# arduheater.net
KiCad netlist of a schematic drawn in EAGLE
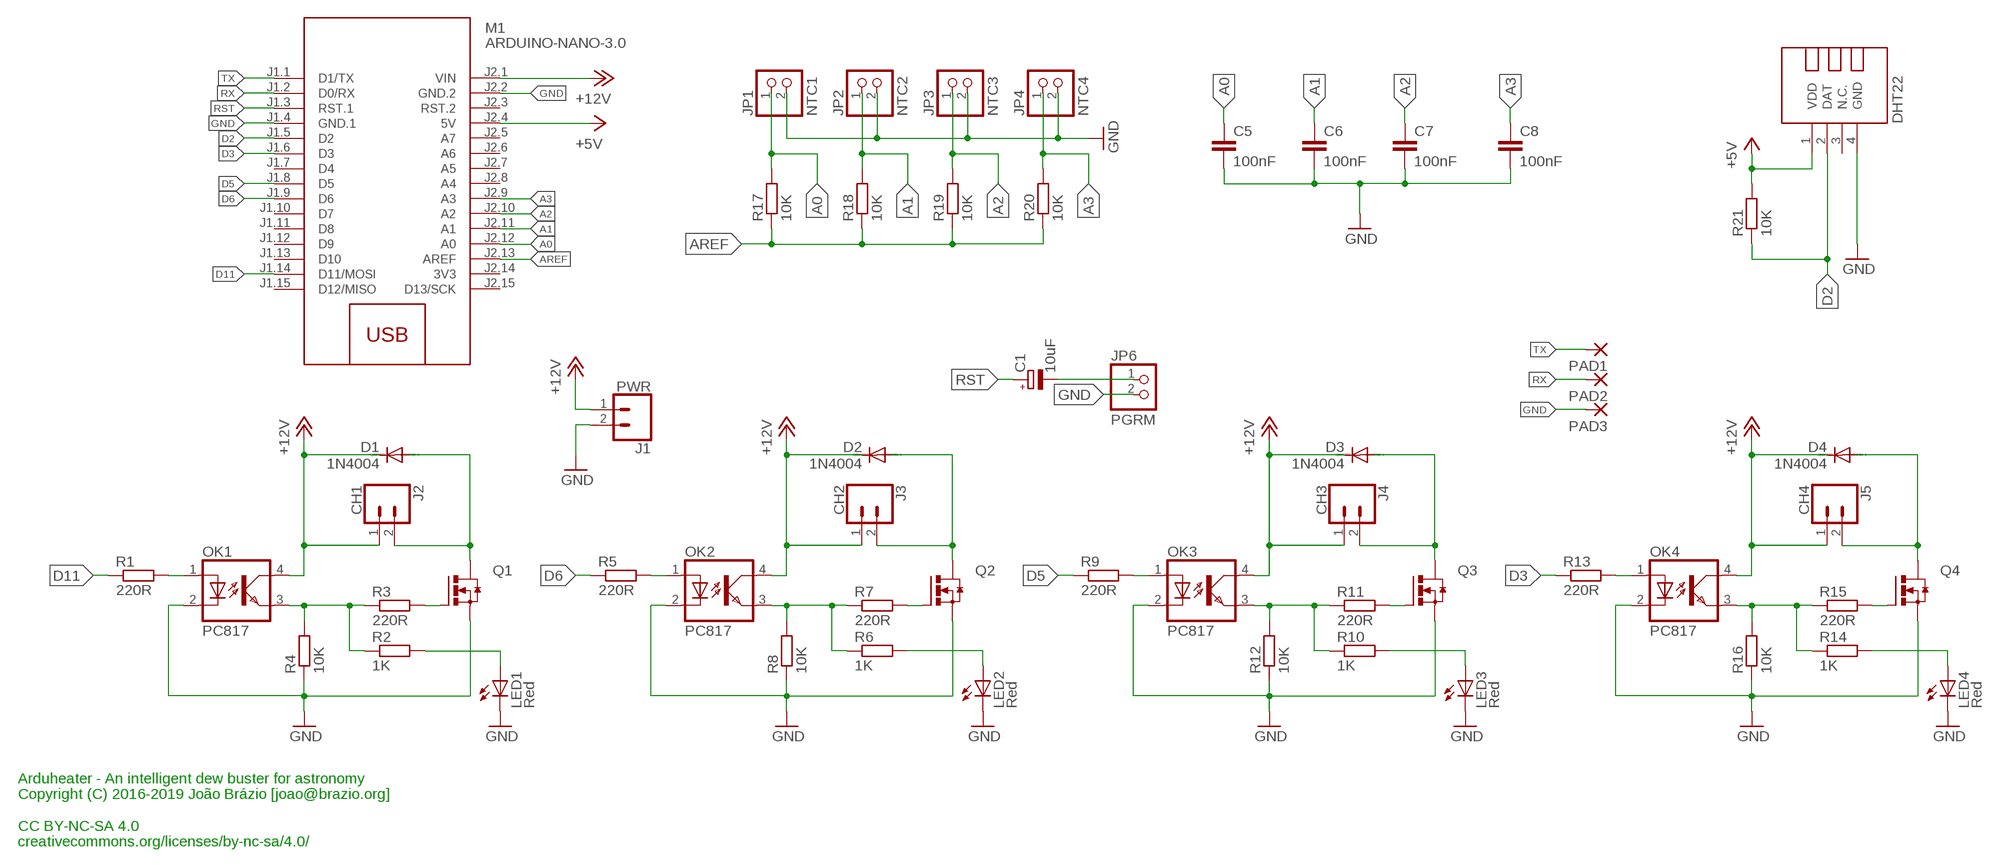
[diagram p0: schematic, sheet 1]

(export (version "E")
  (design (tool "Eeschema 10.0.6"))
  (components
    (comp (ref "C1")
      (value "10uF")
      (footprint "eagle-import:E2,5-6E")
      (libsource (lib "eagle-import") (part "CPOL-EUE2,5-6E"))
    )
    (comp (ref "C5")
      (value "100nF")
      (footprint "eagle-import:C3216")
      (libsource (lib "eagle-import") (part "C-EUC3216"))
    )
    (comp (ref "C6")
      (value "100nF")
      (footprint "eagle-import:C3216")
      (libsource (lib "eagle-import") (part "C-EUC3216"))
    )
    (comp (ref "C7")
      (value "100nF")
      (footprint "eagle-import:C3216")
      (libsource (lib "eagle-import") (part "C-EUC3216"))
    )
    (comp (ref "C8")
      (value "100nF")
      (footprint "eagle-import:C3216")
      (libsource (lib "eagle-import") (part "C-EUC3216"))
    )
    (comp (ref "D1")
      (value "1N4004")
      (footprint "eagle-import:DO41-10")
      (libsource (lib "eagle-import") (part "1N4004"))
    )
    (comp (ref "D2")
      (value "1N4004")
      (footprint "eagle-import:DO41-10")
      (libsource (lib "eagle-import") (part "1N4004"))
    )
    (comp (ref "D3")
      (value "1N4004")
      (footprint "eagle-import:DO41-10")
      (libsource (lib "eagle-import") (part "1N4004"))
    )
    (comp (ref "D4")
      (value "1N4004")
      (footprint "eagle-import:DO41-10")
      (libsource (lib "eagle-import") (part "1N4004"))
    )
    (comp (ref "DHT22")
      (value "TEMP-HUM-SENSOR-DHT22")
      (footprint "eagle-import:TEMP-HUM-SENSOR-DHT22")
      (libsource (lib "eagle-import") (part "TEMP-HUM-SENSOR-DHT22"))
    )
    (comp (ref "J1")
      (value "PWR")
      (footprint "eagle-import:SCREWTERMINAL-5MM-2")
      (libsource (lib "eagle-import") (part "CONN_025MM"))
    )
    (comp (ref "J2")
      (value "CH1")
      (footprint "eagle-import:SCREWTERMINAL-5MM-2")
      (libsource (lib "eagle-import") (part "CONN_025MM"))
    )
    (comp (ref "J3")
      (value "CH2")
      (footprint "eagle-import:SCREWTERMINAL-5MM-2")
      (libsource (lib "eagle-import") (part "CONN_025MM"))
    )
    (comp (ref "J4")
      (value "CH3")
      (footprint "eagle-import:SCREWTERMINAL-5MM-2")
      (libsource (lib "eagle-import") (part "CONN_025MM"))
    )
    (comp (ref "J5")
      (value "CH4")
      (footprint "eagle-import:SCREWTERMINAL-5MM-2")
      (libsource (lib "eagle-import") (part "CONN_025MM"))
    )
    (comp (ref "JP1")
      (value "NTC1")
      (footprint "eagle-import:1X02")
      (libsource (lib "eagle-import") (part "PINHD-1X2"))
    )
    (comp (ref "JP2")
      (value "NTC2")
      (footprint "eagle-import:1X02")
      (libsource (lib "eagle-import") (part "PINHD-1X2"))
    )
    (comp (ref "JP3")
      (value "NTC3")
      (footprint "eagle-import:1X02")
      (libsource (lib "eagle-import") (part "PINHD-1X2"))
    )
    (comp (ref "JP4")
      (value "NTC4")
      (footprint "eagle-import:1X02")
      (libsource (lib "eagle-import") (part "PINHD-1X2"))
    )
    (comp (ref "JP6")
      (value "PGRM")
      (footprint "eagle-import:1X02")
      (libsource (lib "eagle-import") (part "PINHD-1X2"))
    )
    (comp (ref "LED1")
      (value "Red")
      (footprint "eagle-import:LED5MM")
      (libsource (lib "eagle-import") (part "LED5MM"))
    )
    (comp (ref "LED2")
      (value "Red")
      (footprint "eagle-import:LED5MM")
      (libsource (lib "eagle-import") (part "LED5MM"))
    )
    (comp (ref "LED3")
      (value "Red")
      (footprint "eagle-import:LED5MM")
      (libsource (lib "eagle-import") (part "LED5MM"))
    )
    (comp (ref "LED4")
      (value "Red")
      (footprint "eagle-import:LED5MM")
      (libsource (lib "eagle-import") (part "LED5MM"))
    )
    (comp (ref "M1")
      (value "ARDUINO-NANO-3.0")
      (footprint "eagle-import:ARDUINO-NANO-3.0")
      (libsource (lib "eagle-import") (part "ARDUINO-NANO-3.0"))
    )
    (comp (ref "OK1")
      (value "PC817")
      (footprint "eagle-import:DIL04")
      (fields (field (name "MPN") "PC817X4J000F"))
      (libsource (lib "eagle-import") (part "PC817"))
    )
    (comp (ref "OK2")
      (value "PC817")
      (footprint "eagle-import:DIL04")
      (fields (field (name "MPN") "PC817X4J000F"))
      (libsource (lib "eagle-import") (part "PC817"))
    )
    (comp (ref "OK3")
      (value "PC817")
      (footprint "eagle-import:DIL04")
      (fields (field (name "MPN") "PC817X4J000F"))
      (libsource (lib "eagle-import") (part "PC817"))
    )
    (comp (ref "OK4")
      (value "PC817")
      (footprint "eagle-import:DIL04")
      (fields (field (name "MPN") "PC817X4J000F"))
      (libsource (lib "eagle-import") (part "PC817"))
    )
    (comp (ref "PAD1")
      (value "SMD2")
      (footprint "eagle-import:SMD1,27-2,54")
      (libsource (lib "eagle-import") (part "SMD2"))
    )
    (comp (ref "PAD2")
      (value "SMD2")
      (footprint "eagle-import:SMD1,27-2,54")
      (libsource (lib "eagle-import") (part "SMD2"))
    )
    (comp (ref "PAD3")
      (value "SMD2")
      (footprint "eagle-import:SMD1,27-2,54")
      (libsource (lib "eagle-import") (part "SMD2"))
    )
    (comp (ref "Q1")
      (value "IRF3704L-V")
      (footprint "eagle-import:TO262-V")
      (libsource (lib "eagle-import") (part "IRF3704L-V"))
    )
    (comp (ref "Q2")
      (value "IRF3704L-V")
      (footprint "eagle-import:TO262-V")
      (libsource (lib "eagle-import") (part "IRF3704L-V"))
    )
    (comp (ref "Q3")
      (value "IRF3704L-V")
      (footprint "eagle-import:TO262-V")
      (libsource (lib "eagle-import") (part "IRF3704L-V"))
    )
    (comp (ref "Q4")
      (value "IRF3704L-V")
      (footprint "eagle-import:TO262-V")
      (libsource (lib "eagle-import") (part "IRF3704L-V"))
    )
    (comp (ref "R1")
      (value "220R")
      (footprint "eagle-import:M1206")
      (libsource (lib "eagle-import") (part "R-EU_M1206"))
    )
    (comp (ref "R2")
      (value "1K")
      (footprint "eagle-import:M1206")
      (libsource (lib "eagle-import") (part "R-EU_M1206"))
    )
    (comp (ref "R3")
      (value "220R")
      (footprint "eagle-import:M1206")
      (libsource (lib "eagle-import") (part "R-EU_M1206"))
    )
    (comp (ref "R4")
      (value "10K")
      (footprint "eagle-import:M1206")
      (libsource (lib "eagle-import") (part "R-EU_M1206"))
    )
    (comp (ref "R5")
      (value "220R")
      (footprint "eagle-import:M1206")
      (libsource (lib "eagle-import") (part "R-EU_M1206"))
    )
    (comp (ref "R6")
      (value "1K")
      (footprint "eagle-import:M1206")
      (libsource (lib "eagle-import") (part "R-EU_M1206"))
    )
    (comp (ref "R7")
      (value "220R")
      (footprint "eagle-import:M1206")
      (libsource (lib "eagle-import") (part "R-EU_M1206"))
    )
    (comp (ref "R8")
      (value "10K")
      (footprint "eagle-import:M1206")
      (libsource (lib "eagle-import") (part "R-EU_M1206"))
    )
    (comp (ref "R9")
      (value "220R")
      (footprint "eagle-import:M1206")
      (libsource (lib "eagle-import") (part "R-EU_M1206"))
    )
    (comp (ref "R10")
      (value "1K")
      (footprint "eagle-import:M1206")
      (libsource (lib "eagle-import") (part "R-EU_M1206"))
    )
    (comp (ref "R11")
      (value "220R")
      (footprint "eagle-import:M1206")
      (libsource (lib "eagle-import") (part "R-EU_M1206"))
    )
    (comp (ref "R12")
      (value "10K")
      (footprint "eagle-import:M1206")
      (libsource (lib "eagle-import") (part "R-EU_M1206"))
    )
    (comp (ref "R13")
      (value "220R")
      (footprint "eagle-import:M1206")
      (libsource (lib "eagle-import") (part "R-EU_M1206"))
    )
    (comp (ref "R14")
      (value "1K")
      (footprint "eagle-import:M1206")
      (libsource (lib "eagle-import") (part "R-EU_M1206"))
    )
    (comp (ref "R15")
      (value "220R")
      (footprint "eagle-import:M1206")
      (libsource (lib "eagle-import") (part "R-EU_M1206"))
    )
    (comp (ref "R16")
      (value "10K")
      (footprint "eagle-import:M1206")
      (libsource (lib "eagle-import") (part "R-EU_M1206"))
    )
    (comp (ref "R17")
      (value "10K")
      (footprint "eagle-import:M1206")
      (libsource (lib "eagle-import") (part "R-EU_M1206"))
    )
    (comp (ref "R18")
      (value "10K")
      (footprint "eagle-import:M1206")
      (libsource (lib "eagle-import") (part "R-EU_M1206"))
    )
    (comp (ref "R19")
      (value "10K")
      (footprint "eagle-import:M1206")
      (libsource (lib "eagle-import") (part "R-EU_M1206"))
    )
    (comp (ref "R20")
      (value "10K")
      (footprint "eagle-import:M1206")
      (libsource (lib "eagle-import") (part "R-EU_M1206"))
    )
    (comp (ref "R21")
      (value "10K")
      (footprint "eagle-import:M1206")
      (libsource (lib "eagle-import") (part "R-EU_M1206"))
    )
  )
  (nets
    (net (code "1") (name "+5V") (class "Default")
      (node (ref "DHT22") (pin "1") (pinfunction "VDD_1") (pintype "power_in"))
      (node (ref "M1") (pin "J2.4") (pinfunction "5V_J2.4") (pintype "power_in"))
      (node (ref "R21") (pin "2") (pinfunction "2_2") (pintype "passive"))
    )
    (net (code "2") (name "+12V") (class "Default")
      (node (ref "D1") (pin "C") (pinfunction "C_C") (pintype "passive"))
      (node (ref "D2") (pin "C") (pinfunction "C_C") (pintype "passive"))
      (node (ref "D3") (pin "C") (pinfunction "C_C") (pintype "passive"))
      (node (ref "D4") (pin "C") (pinfunction "C_C") (pintype "passive"))
      (node (ref "J1") (pin "1") (pinfunction "1_1") (pintype "passive"))
      (node (ref "J2") (pin "1") (pinfunction "1_1") (pintype "passive"))
      (node (ref "J3") (pin "1") (pinfunction "1_1") (pintype "passive"))
      (node (ref "J4") (pin "1") (pinfunction "1_1") (pintype "passive"))
      (node (ref "J5") (pin "1") (pinfunction "1_1") (pintype "passive"))
      (node (ref "M1") (pin "J2.1") (pinfunction "VIN_J2.1") (pintype "power_in"))
      (node (ref "OK1") (pin "4") (pinfunction "COL_4") (pintype "passive"))
      (node (ref "OK2") (pin "4") (pinfunction "COL_4") (pintype "passive"))
      (node (ref "OK3") (pin "4") (pinfunction "COL_4") (pintype "passive"))
      (node (ref "OK4") (pin "4") (pinfunction "COL_4") (pintype "passive"))
    )
    (net (code "3") (name "/3V3") (class "Default")
      (node (ref "M1") (pin "J2.14") (pinfunction "3V3_J2.14") (pintype "power_in"))
    )
    (net (code "4") (name "A0") (class "Default")
      (node (ref "C5") (pin "1") (pinfunction "1_1") (pintype "passive"))
      (node (ref "JP1") (pin "1") (pinfunction "1_1") (pintype "passive"))
      (node (ref "M1") (pin "J2.12") (pinfunction "A0_J2.12") (pintype "bidirectional"))
      (node (ref "R17") (pin "2") (pinfunction "2_2") (pintype "passive"))
    )
    (net (code "5") (name "A1") (class "Default")
      (node (ref "C6") (pin "1") (pinfunction "1_1") (pintype "passive"))
      (node (ref "JP2") (pin "1") (pinfunction "1_1") (pintype "passive"))
      (node (ref "M1") (pin "J2.11") (pinfunction "A1_J2.11") (pintype "bidirectional"))
      (node (ref "R18") (pin "2") (pinfunction "2_2") (pintype "passive"))
    )
    (net (code "6") (name "A2") (class "Default")
      (node (ref "C7") (pin "1") (pinfunction "1_1") (pintype "passive"))
      (node (ref "JP3") (pin "1") (pinfunction "1_1") (pintype "passive"))
      (node (ref "M1") (pin "J2.10") (pinfunction "A2_J2.10") (pintype "bidirectional"))
      (node (ref "R19") (pin "2") (pinfunction "2_2") (pintype "passive"))
    )
    (net (code "7") (name "A3") (class "Default")
      (node (ref "C8") (pin "1") (pinfunction "1_1") (pintype "passive"))
      (node (ref "JP4") (pin "1") (pinfunction "1_1") (pintype "passive"))
      (node (ref "M1") (pin "J2.9") (pinfunction "A3_J2.9") (pintype "bidirectional"))
      (node (ref "R20") (pin "2") (pinfunction "2_2") (pintype "passive"))
    )
    (net (code "8") (name "AREF") (class "Default")
      (node (ref "M1") (pin "J2.13") (pinfunction "AREF_J2.13") (pintype "bidirectional"))
      (node (ref "R17") (pin "1") (pinfunction "1_1") (pintype "passive"))
      (node (ref "R18") (pin "1") (pinfunction "1_1") (pintype "passive"))
      (node (ref "R19") (pin "1") (pinfunction "1_1") (pintype "passive"))
      (node (ref "R20") (pin "1") (pinfunction "1_1") (pintype "passive"))
    )
    (net (code "9") (name "D2") (class "Default")
      (node (ref "DHT22") (pin "2") (pinfunction "DAT_2") (pintype "bidirectional"))
      (node (ref "M1") (pin "J1.5") (pinfunction "D2_J1.5") (pintype "bidirectional"))
      (node (ref "R21") (pin "1") (pinfunction "1_1") (pintype "passive"))
    )
    (net (code "10") (name "D3") (class "Default")
      (node (ref "M1") (pin "J1.6") (pinfunction "D3_J1.6") (pintype "bidirectional"))
      (node (ref "R13") (pin "1") (pinfunction "1_1") (pintype "passive"))
    )
    (net (code "11") (name "D5") (class "Default")
      (node (ref "M1") (pin "J1.8") (pinfunction "D5_J1.8") (pintype "bidirectional"))
      (node (ref "R9") (pin "1") (pinfunction "1_1") (pintype "passive"))
    )
    (net (code "12") (name "D6") (class "Default")
      (node (ref "M1") (pin "J1.9") (pinfunction "D6_J1.9") (pintype "bidirectional"))
      (node (ref "R5") (pin "1") (pinfunction "1_1") (pintype "passive"))
    )
    (net (code "13") (name "D11") (class "Default")
      (node (ref "M1") (pin "J1.14") (pinfunction "D11/MOSI_J1.14") (pintype "bidirectional"))
      (node (ref "R1") (pin "1") (pinfunction "1_1") (pintype "passive"))
    )
    (net (code "14") (name "GND") (class "Default")
      (node (ref "C5") (pin "2") (pinfunction "2_2") (pintype "passive"))
      (node (ref "C6") (pin "2") (pinfunction "2_2") (pintype "passive"))
      (node (ref "C7") (pin "2") (pinfunction "2_2") (pintype "passive"))
      (node (ref "C8") (pin "2") (pinfunction "2_2") (pintype "passive"))
      (node (ref "DHT22") (pin "4") (pinfunction "GND_4") (pintype "power_in"))
      (node (ref "J1") (pin "2") (pinfunction "2_2") (pintype "passive"))
      (node (ref "JP1") (pin "2") (pinfunction "2_2") (pintype "passive"))
      (node (ref "JP2") (pin "2") (pinfunction "2_2") (pintype "passive"))
      (node (ref "JP3") (pin "2") (pinfunction "2_2") (pintype "passive"))
      (node (ref "JP4") (pin "2") (pinfunction "2_2") (pintype "passive"))
      (node (ref "JP6") (pin "2") (pinfunction "2_2") (pintype "passive"))
      (node (ref "LED1") (pin "K") (pinfunction "C_K") (pintype "passive"))
      (node (ref "LED2") (pin "K") (pinfunction "C_K") (pintype "passive"))
      (node (ref "LED3") (pin "K") (pinfunction "C_K") (pintype "passive"))
      (node (ref "LED4") (pin "K") (pinfunction "C_K") (pintype "passive"))
      (node (ref "M1") (pin "J1.4") (pinfunction "GND.1_J1.4") (pintype "power_in"))
      (node (ref "M1") (pin "J2.2") (pinfunction "GND.2_J2.2") (pintype "power_in"))
      (node (ref "OK1") (pin "2") (pinfunction "C_2") (pintype "passive"))
      (node (ref "OK2") (pin "2") (pinfunction "C_2") (pintype "passive"))
      (node (ref "OK3") (pin "2") (pinfunction "C_2") (pintype "passive"))
      (node (ref "OK4") (pin "2") (pinfunction "C_2") (pintype "passive"))
      (node (ref "PAD3") (pin "1") (pinfunction "P_1") (pintype "passive"))
      (node (ref "Q1") (pin "3") (pinfunction "S_3") (pintype "passive"))
      (node (ref "Q2") (pin "3") (pinfunction "S_3") (pintype "passive"))
      (node (ref "Q3") (pin "3") (pinfunction "S_3") (pintype "passive"))
      (node (ref "Q4") (pin "3") (pinfunction "S_3") (pintype "passive"))
      (node (ref "R12") (pin "1") (pinfunction "1_1") (pintype "passive"))
      (node (ref "R16") (pin "1") (pinfunction "1_1") (pintype "passive"))
      (node (ref "R4") (pin "1") (pinfunction "1_1") (pintype "passive"))
      (node (ref "R8") (pin "1") (pinfunction "1_1") (pintype "passive"))
    )
    (net (code "15") (name "Net-(C1-Pad-)") (class "Default")
      (node (ref "C1") (pin "-") (pinfunction "-_-") (pintype "passive"))
      (node (ref "JP6") (pin "1") (pinfunction "1_1") (pintype "passive"))
    )
    (net (code "16") (name "Net-(LED1-PadA)") (class "Default")
      (node (ref "LED1") (pin "A") (pinfunction "A_A") (pintype "passive"))
      (node (ref "R2") (pin "2") (pinfunction "2_2") (pintype "passive"))
    )
    (net (code "17") (name "Net-(LED2-PadA)") (class "Default")
      (node (ref "LED2") (pin "A") (pinfunction "A_A") (pintype "passive"))
      (node (ref "R6") (pin "2") (pinfunction "2_2") (pintype "passive"))
    )
    (net (code "18") (name "Net-(LED3-PadA)") (class "Default")
      (node (ref "LED3") (pin "A") (pinfunction "A_A") (pintype "passive"))
      (node (ref "R10") (pin "2") (pinfunction "2_2") (pintype "passive"))
    )
    (net (code "19") (name "Net-(LED4-PadA)") (class "Default")
      (node (ref "LED4") (pin "A") (pinfunction "A_A") (pintype "passive"))
      (node (ref "R14") (pin "2") (pinfunction "2_2") (pintype "passive"))
    )
    (net (code "20") (name "Net-(OK1-A)") (class "Default")
      (node (ref "OK1") (pin "1") (pinfunction "A_1") (pintype "passive"))
      (node (ref "R1") (pin "2") (pinfunction "2_2") (pintype "passive"))
    )
    (net (code "21") (name "Net-(OK1-EMIT)") (class "Default")
      (node (ref "OK1") (pin "3") (pinfunction "EMIT_3") (pintype "passive"))
      (node (ref "R2") (pin "1") (pinfunction "1_1") (pintype "passive"))
      (node (ref "R3") (pin "1") (pinfunction "1_1") (pintype "passive"))
      (node (ref "R4") (pin "2") (pinfunction "2_2") (pintype "passive"))
    )
    (net (code "22") (name "Net-(OK2-A)") (class "Default")
      (node (ref "OK2") (pin "1") (pinfunction "A_1") (pintype "passive"))
      (node (ref "R5") (pin "2") (pinfunction "2_2") (pintype "passive"))
    )
    (net (code "23") (name "Net-(OK2-EMIT)") (class "Default")
      (node (ref "OK2") (pin "3") (pinfunction "EMIT_3") (pintype "passive"))
      (node (ref "R6") (pin "1") (pinfunction "1_1") (pintype "passive"))
      (node (ref "R7") (pin "1") (pinfunction "1_1") (pintype "passive"))
      (node (ref "R8") (pin "2") (pinfunction "2_2") (pintype "passive"))
    )
    (net (code "24") (name "Net-(OK3-A)") (class "Default")
      (node (ref "OK3") (pin "1") (pinfunction "A_1") (pintype "passive"))
      (node (ref "R9") (pin "2") (pinfunction "2_2") (pintype "passive"))
    )
    (net (code "25") (name "Net-(OK3-EMIT)") (class "Default")
      (node (ref "OK3") (pin "3") (pinfunction "EMIT_3") (pintype "passive"))
      (node (ref "R10") (pin "1") (pinfunction "1_1") (pintype "passive"))
      (node (ref "R11") (pin "1") (pinfunction "1_1") (pintype "passive"))
      (node (ref "R12") (pin "2") (pinfunction "2_2") (pintype "passive"))
    )
    (net (code "26") (name "Net-(OK4-A)") (class "Default")
      (node (ref "OK4") (pin "1") (pinfunction "A_1") (pintype "passive"))
      (node (ref "R13") (pin "2") (pinfunction "2_2") (pintype "passive"))
    )
    (net (code "27") (name "Net-(OK4-EMIT)") (class "Default")
      (node (ref "OK4") (pin "3") (pinfunction "EMIT_3") (pintype "passive"))
      (node (ref "R14") (pin "1") (pinfunction "1_1") (pintype "passive"))
      (node (ref "R15") (pin "1") (pinfunction "1_1") (pintype "passive"))
      (node (ref "R16") (pin "2") (pinfunction "2_2") (pintype "passive"))
    )
    (net (code "28") (name "Net-(Q1-D)") (class "Default")
      (node (ref "D1") (pin "A") (pinfunction "A_A") (pintype "passive"))
      (node (ref "J2") (pin "2") (pinfunction "2_2") (pintype "passive"))
      (node (ref "Q1") (pin "2") (pinfunction "D_2") (pintype "passive"))
    )
    (net (code "29") (name "Net-(Q1-G)") (class "Default")
      (node (ref "Q1") (pin "1") (pinfunction "G_1") (pintype "passive"))
      (node (ref "R3") (pin "2") (pinfunction "2_2") (pintype "passive"))
    )
    (net (code "30") (name "Net-(Q2-D)") (class "Default")
      (node (ref "D2") (pin "A") (pinfunction "A_A") (pintype "passive"))
      (node (ref "J3") (pin "2") (pinfunction "2_2") (pintype "passive"))
      (node (ref "Q2") (pin "2") (pinfunction "D_2") (pintype "passive"))
    )
    (net (code "31") (name "Net-(Q2-G)") (class "Default")
      (node (ref "Q2") (pin "1") (pinfunction "G_1") (pintype "passive"))
      (node (ref "R7") (pin "2") (pinfunction "2_2") (pintype "passive"))
    )
    (net (code "32") (name "Net-(Q3-D)") (class "Default")
      (node (ref "D3") (pin "A") (pinfunction "A_A") (pintype "passive"))
      (node (ref "J4") (pin "2") (pinfunction "2_2") (pintype "passive"))
      (node (ref "Q3") (pin "2") (pinfunction "D_2") (pintype "passive"))
    )
    (net (code "33") (name "Net-(Q3-G)") (class "Default")
      (node (ref "Q3") (pin "1") (pinfunction "G_1") (pintype "passive"))
      (node (ref "R11") (pin "2") (pinfunction "2_2") (pintype "passive"))
    )
    (net (code "34") (name "Net-(Q4-D)") (class "Default")
      (node (ref "D4") (pin "A") (pinfunction "A_A") (pintype "passive"))
      (node (ref "J5") (pin "2") (pinfunction "2_2") (pintype "passive"))
      (node (ref "Q4") (pin "2") (pinfunction "D_2") (pintype "passive"))
    )
    (net (code "35") (name "Net-(Q4-G)") (class "Default")
      (node (ref "Q4") (pin "1") (pinfunction "G_1") (pintype "passive"))
      (node (ref "R15") (pin "2") (pinfunction "2_2") (pintype "passive"))
    )
    (net (code "36") (name "RST") (class "Default")
      (node (ref "C1") (pin "+") (pinfunction "+_+") (pintype "passive"))
      (node (ref "M1") (pin "J1.3") (pinfunction "RST.1_J1.3") (pintype "bidirectional"))
    )
    (net (code "37") (name "RX") (class "Default")
      (node (ref "M1") (pin "J1.2") (pinfunction "D0/RX_J1.2") (pintype "bidirectional"))
      (node (ref "PAD2") (pin "1") (pinfunction "P_1") (pintype "passive"))
    )
    (net (code "38") (name "TX") (class "Default")
      (node (ref "M1") (pin "J1.1") (pinfunction "D1/TX_J1.1") (pintype "bidirectional"))
      (node (ref "PAD1") (pin "1") (pinfunction "P_1") (pintype "passive"))
    )
    (net (code "39") (name "unconnected-(DHT22-N.C.-Pad3)") (class "Default")
      (node (ref "DHT22") (pin "3") (pinfunction "N.C._3") (pintype "passive"))
    )
    (net (code "40") (name "unconnected-(M1-A4-PadJ2.8)") (class "Default")
      (node (ref "M1") (pin "J2.8") (pinfunction "A4_J2.8") (pintype "bidirectional"))
    )
    (net (code "41") (name "unconnected-(M1-A5-PadJ2.7)") (class "Default")
      (node (ref "M1") (pin "J2.7") (pinfunction "A5_J2.7") (pintype "bidirectional"))
    )
    (net (code "42") (name "unconnected-(M1-A6-PadJ2.6)") (class "Default")
      (node (ref "M1") (pin "J2.6") (pinfunction "A6_J2.6") (pintype "bidirectional"))
    )
    (net (code "43") (name "unconnected-(M1-A7-PadJ2.5)") (class "Default")
      (node (ref "M1") (pin "J2.5") (pinfunction "A7_J2.5") (pintype "bidirectional"))
    )
    (net (code "44") (name "unconnected-(M1-D4-PadJ1.7)") (class "Default")
      (node (ref "M1") (pin "J1.7") (pinfunction "D4_J1.7") (pintype "bidirectional"))
    )
    (net (code "45") (name "unconnected-(M1-D7-PadJ1.10)") (class "Default")
      (node (ref "M1") (pin "J1.10") (pinfunction "D7_J1.10") (pintype "bidirectional"))
    )
    (net (code "46") (name "unconnected-(M1-D8-PadJ1.11)") (class "Default")
      (node (ref "M1") (pin "J1.11") (pinfunction "D8_J1.11") (pintype "bidirectional"))
    )
    (net (code "47") (name "unconnected-(M1-D9-PadJ1.12)") (class "Default")
      (node (ref "M1") (pin "J1.12") (pinfunction "D9_J1.12") (pintype "bidirectional"))
    )
    (net (code "48") (name "unconnected-(M1-D10-PadJ1.13)") (class "Default")
      (node (ref "M1") (pin "J1.13") (pinfunction "D10_J1.13") (pintype "bidirectional"))
    )
    (net (code "49") (name "unconnected-(M1-D12{slash}MISO-PadJ1.15)") (class "Default")
      (node (ref "M1") (pin "J1.15") (pinfunction "D12/MISO_J1.15") (pintype "bidirectional"))
    )
    (net (code "50") (name "unconnected-(M1-D13{slash}SCK-PadJ2.15)") (class "Default")
      (node (ref "M1") (pin "J2.15") (pinfunction "D13/SCK_J2.15") (pintype "bidirectional"))
    )
    (net (code "51") (name "unconnected-(M1-RST.2-PadJ2.3)") (class "Default")
      (node (ref "M1") (pin "J2.3") (pinfunction "RST.2_J2.3") (pintype "bidirectional"))
    )
  )
)
